# Nav_Buttons.net
KiCad netlist of a schematic drawn in Altium Designer
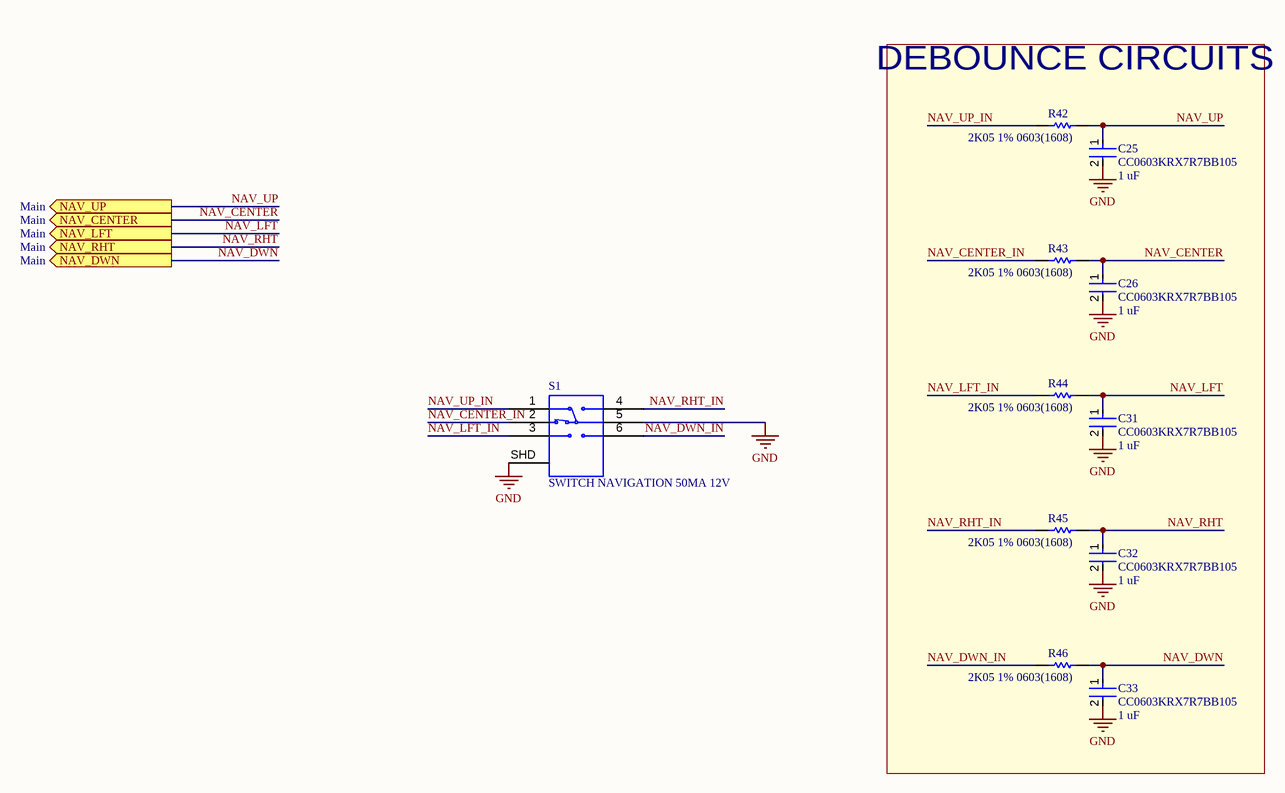
[diagram p0: Nav_Buttons.SchDoc]

(export (version "E")
  (design (tool "Eeschema 10.0.6"))
  (components
    (comp (ref "C25")
      (value "CC0603KRX7R7BB105")
      (footprint "FP-CC0603-DA-MFG")
      (description "CAP CER 1UF 16V X7R 0603")
      (fields
        (field (name "TOLERANCE") "0.1")
        (field (name "MANUFACTURER") "YAGEO")
        (field (name "ALTIUM_VALUE") "1 uF")
      )
      (libsource (lib "Altium Content Vault") (part "11868f565c42a9108669ba33697ecf6"))
    )
    (comp (ref "C26")
      (value "CC0603KRX7R7BB105")
      (footprint "FP-CC0603-DA-MFG")
      (description "CAP CER 1UF 16V X7R 0603")
      (fields
        (field (name "TOLERANCE") "0.1")
        (field (name "MANUFACTURER") "YAGEO")
        (field (name "ALTIUM_VALUE") "1 uF")
      )
      (libsource (lib "Altium Content Vault") (part "11868f565c42a9108669ba33697ecf6"))
    )
    (comp (ref "C31")
      (value "CC0603KRX7R7BB105")
      (footprint "FP-CC0603-DA-MFG")
      (description "CAP CER 1UF 16V X7R 0603")
      (fields
        (field (name "TOLERANCE") "0.1")
        (field (name "MANUFACTURER") "YAGEO")
        (field (name "ALTIUM_VALUE") "1 uF")
      )
      (libsource (lib "Altium Content Vault") (part "11868f565c42a9108669ba33697ecf6"))
    )
    (comp (ref "C32")
      (value "CC0603KRX7R7BB105")
      (footprint "FP-CC0603-DA-MFG")
      (description "CAP CER 1UF 16V X7R 0603")
      (fields
        (field (name "TOLERANCE") "0.1")
        (field (name "MANUFACTURER") "YAGEO")
        (field (name "ALTIUM_VALUE") "1 uF")
      )
      (libsource (lib "Altium Content Vault") (part "11868f565c42a9108669ba33697ecf6"))
    )
    (comp (ref "C33")
      (value "CC0603KRX7R7BB105")
      (footprint "FP-CC0603-DA-MFG")
      (description "CAP CER 1UF 16V X7R 0603")
      (fields
        (field (name "TOLERANCE") "0.1")
        (field (name "MANUFACTURER") "YAGEO")
        (field (name "ALTIUM_VALUE") "1 uF")
      )
      (libsource (lib "Altium Content Vault") (part "11868f565c42a9108669ba33697ecf6"))
    )
    (comp (ref "R42")
      (value "2K05 1% 0603(1608)")
      (footprint "RESC0603(1608)_L")
      (description "2K05 0.1W 1% 0603 (1608 Metric)  SMD")
      (fields (field (name "TOLERANCE") "1 %") (field (name "POWER") "0.1 W"))
      (libsource (lib "Altium Content Vault") (part "RES"))
    )
    (comp (ref "R43")
      (value "2K05 1% 0603(1608)")
      (footprint "RESC0603(1608)_L")
      (description "2K05 0.1W 1% 0603 (1608 Metric)  SMD")
      (fields (field (name "TOLERANCE") "1 %") (field (name "POWER") "0.1 W"))
      (libsource (lib "Altium Content Vault") (part "RES"))
    )
    (comp (ref "R44")
      (value "2K05 1% 0603(1608)")
      (footprint "RESC0603(1608)_L")
      (description "2K05 0.1W 1% 0603 (1608 Metric)  SMD")
      (fields (field (name "TOLERANCE") "1 %") (field (name "POWER") "0.1 W"))
      (libsource (lib "Altium Content Vault") (part "RES"))
    )
    (comp (ref "R45")
      (value "2K05 1% 0603(1608)")
      (footprint "RESC0603(1608)_L")
      (description "2K05 0.1W 1% 0603 (1608 Metric)  SMD")
      (fields (field (name "TOLERANCE") "1 %") (field (name "POWER") "0.1 W"))
      (libsource (lib "Altium Content Vault") (part "RES"))
    )
    (comp (ref "R46")
      (value "2K05 1% 0603(1608)")
      (footprint "RESC0603(1608)_L")
      (description "2K05 0.1W 1% 0603 (1608 Metric)  SMD")
      (fields (field (name "TOLERANCE") "1 %") (field (name "POWER") "0.1 W"))
      (libsource (lib "Altium Content Vault") (part "RES"))
    )
    (comp (ref "S1")
      (value "SWITCH NAVIGATION 50MA 12V")
      (footprint "ProtoWatch_PcbLib:SW_JS1400AFQ")
      (description "Navigation Switch, 2 - Axis Digital (Mechanical Switch) Output")
      (fields (field (name "MF") "E-Switch") (field (name "DIGI-KEY_PART_NUMBER") "EG5857-ND"))
      (libsource (lib "ProtoWatch_SchLib") (part "JS1400AFQ"))
    )
  )
  (nets
    (net (code "1") (name "/NAV_CENTER") (class "Default")
      (node (ref "C26") (pin "1") (pinfunction "1_1") (pintype "passive"))
      (node (ref "R43") (pin "2") (pinfunction "2_2") (pintype "passive"))
    )
    (net (code "2") (name "/NAV_CENTER_IN") (class "Default")
      (node (ref "R43") (pin "1") (pinfunction "1_1") (pintype "passive"))
      (node (ref "S1") (pin "2") (pinfunction "2_2") (pintype "passive"))
    )
    (net (code "3") (name "/NAV_DWN") (class "Default")
      (node (ref "C33") (pin "1") (pinfunction "1_1") (pintype "passive"))
      (node (ref "R46") (pin "2") (pinfunction "2_2") (pintype "passive"))
    )
    (net (code "4") (name "/NAV_DWN_IN") (class "Default")
      (node (ref "R46") (pin "1") (pinfunction "1_1") (pintype "passive"))
      (node (ref "S1") (pin "6") (pinfunction "6_6") (pintype "passive"))
    )
    (net (code "5") (name "/NAV_LFT") (class "Default")
      (node (ref "C31") (pin "1") (pinfunction "1_1") (pintype "passive"))
      (node (ref "R44") (pin "2") (pinfunction "2_2") (pintype "passive"))
    )
    (net (code "6") (name "/NAV_LFT_IN") (class "Default")
      (node (ref "R44") (pin "1") (pinfunction "1_1") (pintype "passive"))
      (node (ref "S1") (pin "3") (pinfunction "3_3") (pintype "passive"))
    )
    (net (code "7") (name "/NAV_RHT") (class "Default")
      (node (ref "C32") (pin "1") (pinfunction "1_1") (pintype "passive"))
      (node (ref "R45") (pin "2") (pinfunction "2_2") (pintype "passive"))
    )
    (net (code "8") (name "/NAV_RHT_IN") (class "Default")
      (node (ref "R45") (pin "1") (pinfunction "1_1") (pintype "passive"))
      (node (ref "S1") (pin "4") (pinfunction "4_4") (pintype "passive"))
    )
    (net (code "9") (name "/NAV_UP") (class "Default")
      (node (ref "C25") (pin "1") (pinfunction "1_1") (pintype "passive"))
      (node (ref "R42") (pin "2") (pinfunction "2_2") (pintype "passive"))
    )
    (net (code "10") (name "/NAV_UP_IN") (class "Default")
      (node (ref "R42") (pin "1") (pinfunction "1_1") (pintype "passive"))
      (node (ref "S1") (pin "1") (pinfunction "1_1") (pintype "passive"))
    )
    (net (code "11") (name "GND") (class "Default")
      (node (ref "C25") (pin "2") (pinfunction "2_2") (pintype "passive"))
      (node (ref "C26") (pin "2") (pinfunction "2_2") (pintype "passive"))
      (node (ref "C31") (pin "2") (pinfunction "2_2") (pintype "passive"))
      (node (ref "C32") (pin "2") (pinfunction "2_2") (pintype "passive"))
      (node (ref "C33") (pin "2") (pinfunction "2_2") (pintype "passive"))
      (node (ref "S1") (pin "5") (pinfunction "5_5") (pintype "passive"))
      (node (ref "S1") (pin "SHD") (pinfunction "SHIELD_SHD") (pintype "passive"))
    )
  )
)
